# PowerConvert.net
KiCad netlist of a schematic drawn in Altium Designer
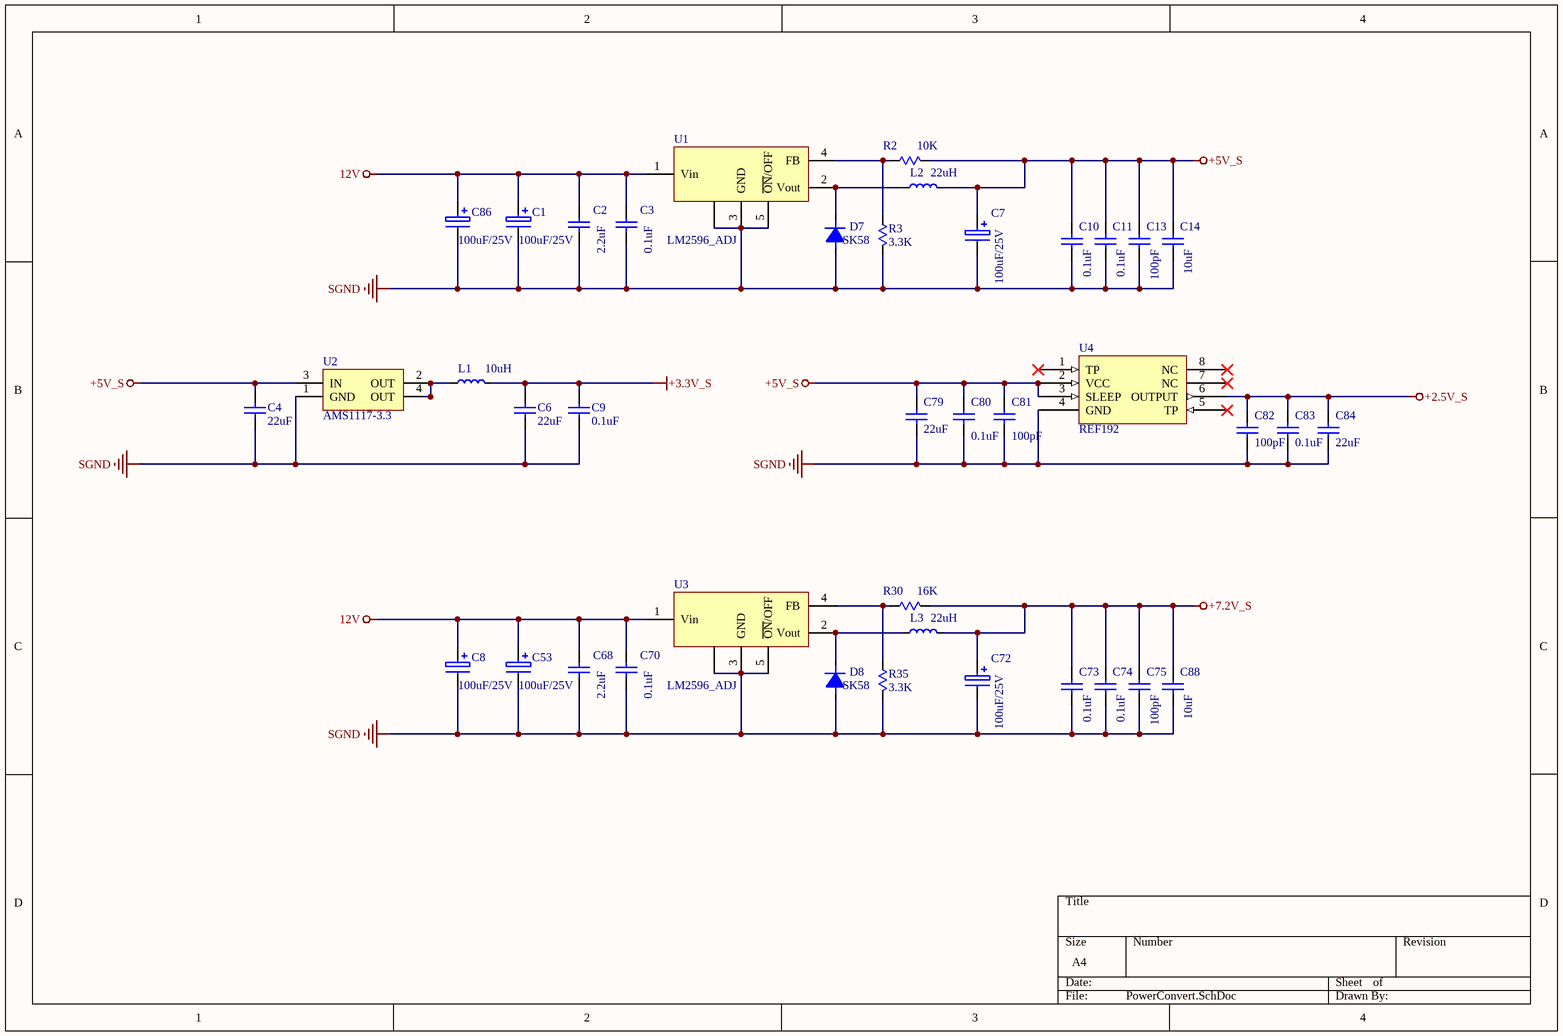
[diagram p0: PowerConvert.SchDoc]

(export (version "E")
  (design (tool "Eeschema 10.0.6"))
  (components
    (comp (ref "C1")
      (value "100uF/25V")
      (footprint "CT7343-E-S")
      (description "Electrolytic Capacitor")
      (libsource (lib "*") (part "ELECTRO"))
    )
    (comp (ref "C2")
      (value "2.2uF")
      (footprint "C1206")
      (description "CAP")
      (fields (field (name "PUBLISHER") "Altium Limited"))
      (libsource (lib "Passive Components Class") (part "CAP"))
    )
    (comp (ref "C3")
      (value "0.1uF")
      (footprint "C0805")
      (description "CAP")
      (fields (field (name "PUBLISHER") "Altium Limited"))
      (libsource (lib "Passive Components Class") (part "CAP"))
    )
    (comp (ref "C4")
      (value "22uF")
      (footprint "C1206")
      (description "CAP")
      (fields (field (name "PUBLISHER") "Altium Limited"))
      (libsource (lib "Passive Components Class") (part "CAP"))
    )
    (comp (ref "C6")
      (value "22uF")
      (footprint "C1206")
      (description "CAP")
      (fields (field (name "PUBLISHER") "Altium Limited"))
      (libsource (lib "Passive Components Class") (part "CAP"))
    )
    (comp (ref "C7")
      (value "100uF/25V")
      (footprint "CT7343-E-S")
      (description "Electrolytic Capacitor")
      (libsource (lib "*") (part "ELECTRO"))
    )
    (comp (ref "C8")
      (value "100uF/25V")
      (footprint "CT7343-E-S")
      (description "Electrolytic Capacitor")
      (libsource (lib "*") (part "ELECTRO"))
    )
    (comp (ref "C9")
      (value "0.1uF")
      (footprint "C0805")
      (description "CAP")
      (fields (field (name "PUBLISHER") "Altium Limited"))
      (libsource (lib "Passive Components Class") (part "CAP"))
    )
    (comp (ref "C10")
      (value "0.1uF")
      (footprint "C0805")
      (description "CAP")
      (fields (field (name "PUBLISHER") "Altium Limited"))
      (libsource (lib "Passive Components Class") (part "CAP"))
    )
    (comp (ref "C11")
      (value "0.1uF")
      (footprint "C0805")
      (description "CAP")
      (fields (field (name "PUBLISHER") "Altium Limited"))
      (libsource (lib "Passive Components Class") (part "CAP"))
    )
    (comp (ref "C13")
      (value "100pF")
      (footprint "C0805")
      (description "CAP")
      (fields (field (name "PUBLISHER") "Altium Limited"))
      (libsource (lib "Passive Components Class") (part "CAP"))
    )
    (comp (ref "C14")
      (value "10uF")
      (footprint "C0805")
      (description "CAP")
      (fields (field (name "PUBLISHER") "Altium Limited"))
      (libsource (lib "Passive Components Class") (part "CAP"))
    )
    (comp (ref "C53")
      (value "100uF/25V")
      (footprint "CT7343-E-S")
      (description "Electrolytic Capacitor")
      (libsource (lib "*") (part "ELECTRO"))
    )
    (comp (ref "C68")
      (value "2.2uF")
      (footprint "C1206")
      (description "CAP")
      (fields (field (name "PUBLISHER") "Altium Limited"))
      (libsource (lib "Passive Components Class") (part "CAP"))
    )
    (comp (ref "C70")
      (value "0.1uF")
      (footprint "C0805")
      (description "CAP")
      (fields (field (name "PUBLISHER") "Altium Limited"))
      (libsource (lib "Passive Components Class") (part "CAP"))
    )
    (comp (ref "C72")
      (value "100uF/25V")
      (footprint "CT7343-E-S")
      (description "Electrolytic Capacitor")
      (libsource (lib "*") (part "ELECTRO"))
    )
    (comp (ref "C73")
      (value "0.1uF")
      (footprint "C0805")
      (description "CAP")
      (fields (field (name "PUBLISHER") "Altium Limited"))
      (libsource (lib "Passive Components Class") (part "CAP"))
    )
    (comp (ref "C74")
      (value "0.1uF")
      (footprint "C0805")
      (description "CAP")
      (fields (field (name "PUBLISHER") "Altium Limited"))
      (libsource (lib "Passive Components Class") (part "CAP"))
    )
    (comp (ref "C75")
      (value "100pF")
      (footprint "C0805")
      (description "CAP")
      (fields (field (name "PUBLISHER") "Altium Limited"))
      (libsource (lib "Passive Components Class") (part "CAP"))
    )
    (comp (ref "C79")
      (value "22uF")
      (footprint "C1206")
      (description "CAP")
      (fields (field (name "PUBLISHER") "Altium Limited"))
      (libsource (lib "Passive Components Class") (part "CAP"))
    )
    (comp (ref "C80")
      (value "0.1uF")
      (footprint "C0805")
      (description "CAP")
      (fields (field (name "PUBLISHER") "Altium Limited"))
      (libsource (lib "Passive Components Class") (part "CAP"))
    )
    (comp (ref "C81")
      (value "100pF")
      (footprint "C0805")
      (description "CAP")
      (fields (field (name "PUBLISHER") "Altium Limited"))
      (libsource (lib "Passive Components Class") (part "CAP"))
    )
    (comp (ref "C82")
      (value "100pF")
      (footprint "C0805")
      (description "CAP")
      (fields (field (name "PUBLISHER") "Altium Limited"))
      (libsource (lib "Passive Components Class") (part "CAP"))
    )
    (comp (ref "C83")
      (value "0.1uF")
      (footprint "C0805")
      (description "CAP")
      (fields (field (name "PUBLISHER") "Altium Limited"))
      (libsource (lib "Passive Components Class") (part "CAP"))
    )
    (comp (ref "C84")
      (value "22uF")
      (footprint "C1206")
      (description "CAP")
      (fields (field (name "PUBLISHER") "Altium Limited"))
      (libsource (lib "Passive Components Class") (part "CAP"))
    )
    (comp (ref "C86")
      (value "100uF/25V")
      (footprint "CT7343-E-S")
      (description "Electrolytic Capacitor")
      (libsource (lib "*") (part "ELECTRO"))
    )
    (comp (ref "C88")
      (value "10uF")
      (footprint "C0805")
      (description "CAP")
      (fields (field (name "PUBLISHER") "Altium Limited"))
      (libsource (lib "Passive Components Class") (part "CAP"))
    )
    (comp (ref "D7")
      (value "SK58")
      (footprint "SMB")
      (description "Diode")
      (libsource (lib "*") (part "DIODE1"))
    )
    (comp (ref "D8")
      (value "SK58")
      (footprint "SMB")
      (description "Diode")
      (libsource (lib "*") (part "DIODE1"))
    )
    (comp (ref "L1")
      (value "10uH")
      (footprint "L0805-C")
      (description "INDUCTOR")
      (fields (field (name "PUBLISHER") "Altium Limited"))
      (libsource (lib "Passive Components Class") (part "INDUCTOR"))
    )
    (comp (ref "L2")
      (value "22uH")
      (footprint "L5050-P")
      (description "INDUCTOR")
      (fields (field (name "PUBLISHER") "Altium Limited"))
      (libsource (lib "Passive Components Class") (part "INDUCTOR"))
    )
    (comp (ref "L3")
      (value "22uH")
      (footprint "L5050-P")
      (description "INDUCTOR")
      (fields (field (name "PUBLISHER") "Altium Limited"))
      (libsource (lib "Passive Components Class") (part "INDUCTOR"))
    )
    (comp (ref "R2")
      (value "10K")
      (footprint "R0805")
      (description "Resistor")
      (fields (field (name "PUBLISHER") "Altium Limited"))
      (libsource (lib "Passive Components Class") (part "RES"))
    )
    (comp (ref "R3")
      (value "3.3K")
      (footprint "R0805")
      (description "Resistor")
      (fields (field (name "PUBLISHER") "Altium Limited"))
      (libsource (lib "Passive Components Class") (part "RES"))
    )
    (comp (ref "R30")
      (value "16K")
      (footprint "R0805")
      (description "Resistor")
      (fields (field (name "PUBLISHER") "Altium Limited"))
      (libsource (lib "Passive Components Class") (part "RES"))
    )
    (comp (ref "R35")
      (value "3.3K")
      (footprint "R0805")
      (description "Resistor")
      (fields (field (name "PUBLISHER") "Altium Limited"))
      (libsource (lib "Passive Components Class") (part "RES"))
    )
    (comp (ref "U1") (value "LM2596_ADJ") (footprint "TO263") (libsource (lib "*") (part "LM2575")))
    (comp (ref "U2")
      (value "AMS1117-3.3")
      (footprint "SOT-223")
      (description "800mA and 1A Low Dropout Positive Regulator 2.85V, 3.3V, 5V, and Adjustable")
      (fields (field (name "PUBLISHER") "Altium Limited"))
      (libsource (lib "BB Power Mgt Voltage Regulator") (part "REG1117-3.3"))
    )
    (comp (ref "U3") (value "LM2596_ADJ") (footprint "TO263") (libsource (lib "*") (part "LM2575")))
    (comp (ref "U4") (value "REF192") (footprint "SO-8") (libsource (lib "tribute") (part "REF192/5/7")))
  )
  (nets
    (net (code "1") (name "+2.5V_S") (class "Default")
      (node (ref "C82") (pin "2") (pinfunction "2_2") (pintype "passive"))
      (node (ref "C83") (pin "2") (pinfunction "2_2") (pintype "passive"))
      (node (ref "C84") (pin "2") (pinfunction "2_2") (pintype "passive"))
      (node (ref "U4") (pin "6") (pinfunction "OUTPUT_6") (pintype "output"))
    )
    (net (code "2") (name "+3.3V_S") (class "Default")
      (node (ref "C6") (pin "1") (pinfunction "1_1") (pintype "passive"))
      (node (ref "C9") (pin "2") (pinfunction "2_2") (pintype "passive"))
      (node (ref "L1") (pin "1") (pinfunction "1_1") (pintype "passive"))
    )
    (net (code "3") (name "+5V_S") (class "Default")
      (node (ref "C10") (pin "2") (pinfunction "2_2") (pintype "passive"))
      (node (ref "C11") (pin "2") (pinfunction "2_2") (pintype "passive"))
      (node (ref "C13") (pin "2") (pinfunction "2_2") (pintype "passive"))
      (node (ref "C14") (pin "2") (pinfunction "2_2") (pintype "passive"))
      (node (ref "C4") (pin "1") (pinfunction "1_1") (pintype "passive"))
      (node (ref "C7") (pin "1") (pinfunction "1_1") (pintype "passive"))
      (node (ref "C79") (pin "2") (pinfunction "2_2") (pintype "passive"))
      (node (ref "C80") (pin "2") (pinfunction "2_2") (pintype "passive"))
      (node (ref "C81") (pin "2") (pinfunction "2_2") (pintype "passive"))
      (node (ref "L2") (pin "1") (pinfunction "1_1") (pintype "passive"))
      (node (ref "R2") (pin "1") (pinfunction "1_1") (pintype "passive"))
      (node (ref "U2") (pin "3") (pinfunction "IN_3") (pintype "power_in"))
      (node (ref "U4") (pin "2") (pinfunction "VCC_2") (pintype "input"))
      (node (ref "U4") (pin "3") (pinfunction "SLEEP_3") (pintype "input"))
    )
    (net (code "4") (name "+7.2V_S") (class "Default")
      (node (ref "C72") (pin "1") (pinfunction "1_1") (pintype "passive"))
      (node (ref "C73") (pin "2") (pinfunction "2_2") (pintype "passive"))
      (node (ref "C74") (pin "2") (pinfunction "2_2") (pintype "passive"))
      (node (ref "C75") (pin "2") (pinfunction "2_2") (pintype "passive"))
      (node (ref "C88") (pin "2") (pinfunction "2_2") (pintype "passive"))
      (node (ref "L3") (pin "1") (pinfunction "1_1") (pintype "passive"))
      (node (ref "R30") (pin "1") (pinfunction "1_1") (pintype "passive"))
    )
    (net (code "5") (name "12V") (class "Default")
      (node (ref "C1") (pin "1") (pinfunction "1_1") (pintype "passive"))
      (node (ref "C2") (pin "2") (pinfunction "2_2") (pintype "passive"))
      (node (ref "C3") (pin "2") (pinfunction "2_2") (pintype "passive"))
      (node (ref "C53") (pin "1") (pinfunction "1_1") (pintype "passive"))
      (node (ref "C68") (pin "2") (pinfunction "2_2") (pintype "passive"))
      (node (ref "C70") (pin "2") (pinfunction "2_2") (pintype "passive"))
      (node (ref "C8") (pin "1") (pinfunction "1_1") (pintype "passive"))
      (node (ref "C86") (pin "1") (pinfunction "1_1") (pintype "passive"))
      (node (ref "U1") (pin "1") (pinfunction "Vin_1") (pintype "power_in"))
      (node (ref "U3") (pin "1") (pinfunction "Vin_1") (pintype "power_in"))
    )
    (net (code "6") (name "Net-(D7-K)") (class "Default")
      (node (ref "D7") (pin "2") (pinfunction "K_2") (pintype "passive"))
      (node (ref "L2") (pin "2") (pinfunction "2_2") (pintype "passive"))
      (node (ref "U1") (pin "2") (pinfunction "Vout_2") (pintype "power_in"))
    )
    (net (code "7") (name "Net-(D8-K)") (class "Default")
      (node (ref "D8") (pin "2") (pinfunction "K_2") (pintype "passive"))
      (node (ref "L3") (pin "2") (pinfunction "2_2") (pintype "passive"))
      (node (ref "U3") (pin "2") (pinfunction "Vout_2") (pintype "power_in"))
    )
    (net (code "8") (name "Net-(L1-Pad2)") (class "Default")
      (node (ref "L1") (pin "2") (pinfunction "2_2") (pintype "passive"))
      (node (ref "U2") (pin "2") (pinfunction "OUT_2") (pintype "power_in"))
      (node (ref "U2") (pin "4") (pinfunction "OUT_4") (pintype "power_in"))
    )
    (net (code "9") (name "Net-(U1-FB)") (class "Default")
      (node (ref "R2") (pin "2") (pinfunction "2_2") (pintype "passive"))
      (node (ref "R3") (pin "2") (pinfunction "2_2") (pintype "passive"))
      (node (ref "U1") (pin "4") (pinfunction "FB_4") (pintype "passive"))
    )
    (net (code "10") (name "Net-(U3-FB)") (class "Default")
      (node (ref "R30") (pin "2") (pinfunction "2_2") (pintype "passive"))
      (node (ref "R35") (pin "2") (pinfunction "2_2") (pintype "passive"))
      (node (ref "U3") (pin "4") (pinfunction "FB_4") (pintype "passive"))
    )
    (net (code "11") (name "SGND") (class "Default")
      (node (ref "C1") (pin "2") (pinfunction "2_2") (pintype "passive"))
      (node (ref "C10") (pin "1") (pinfunction "1_1") (pintype "passive"))
      (node (ref "C11") (pin "1") (pinfunction "1_1") (pintype "passive"))
      (node (ref "C13") (pin "1") (pinfunction "1_1") (pintype "passive"))
      (node (ref "C14") (pin "1") (pinfunction "1_1") (pintype "passive"))
      (node (ref "C2") (pin "1") (pinfunction "1_1") (pintype "passive"))
      (node (ref "C3") (pin "1") (pinfunction "1_1") (pintype "passive"))
      (node (ref "C4") (pin "2") (pinfunction "2_2") (pintype "passive"))
      (node (ref "C53") (pin "2") (pinfunction "2_2") (pintype "passive"))
      (node (ref "C6") (pin "2") (pinfunction "2_2") (pintype "passive"))
      (node (ref "C68") (pin "1") (pinfunction "1_1") (pintype "passive"))
      (node (ref "C7") (pin "2") (pinfunction "2_2") (pintype "passive"))
      (node (ref "C70") (pin "1") (pinfunction "1_1") (pintype "passive"))
      (node (ref "C72") (pin "2") (pinfunction "2_2") (pintype "passive"))
      (node (ref "C73") (pin "1") (pinfunction "1_1") (pintype "passive"))
      (node (ref "C74") (pin "1") (pinfunction "1_1") (pintype "passive"))
      (node (ref "C75") (pin "1") (pinfunction "1_1") (pintype "passive"))
      (node (ref "C79") (pin "1") (pinfunction "1_1") (pintype "passive"))
      (node (ref "C8") (pin "2") (pinfunction "2_2") (pintype "passive"))
      (node (ref "C80") (pin "1") (pinfunction "1_1") (pintype "passive"))
      (node (ref "C81") (pin "1") (pinfunction "1_1") (pintype "passive"))
      (node (ref "C82") (pin "1") (pinfunction "1_1") (pintype "passive"))
      (node (ref "C83") (pin "1") (pinfunction "1_1") (pintype "passive"))
      (node (ref "C84") (pin "1") (pinfunction "1_1") (pintype "passive"))
      (node (ref "C86") (pin "2") (pinfunction "2_2") (pintype "passive"))
      (node (ref "C88") (pin "1") (pinfunction "1_1") (pintype "passive"))
      (node (ref "C9") (pin "1") (pinfunction "1_1") (pintype "passive"))
      (node (ref "D7") (pin "1") (pinfunction "A_1") (pintype "passive"))
      (node (ref "D8") (pin "1") (pinfunction "A_1") (pintype "passive"))
      (node (ref "R3") (pin "1") (pinfunction "1_1") (pintype "passive"))
      (node (ref "R35") (pin "1") (pinfunction "1_1") (pintype "passive"))
      (node (ref "U1") (pin "0") (pinfunction "GND_0") (pintype "passive"))
      (node (ref "U1") (pin "3") (pinfunction "GND_3") (pintype "power_in"))
      (node (ref "U1") (pin "5") (pinfunction "~{ON}/OFF_5") (pintype "passive"))
      (node (ref "U2") (pin "1") (pinfunction "GND_1") (pintype "power_in"))
      (node (ref "U3") (pin "0") (pinfunction "GND_0") (pintype "passive"))
      (node (ref "U3") (pin "3") (pinfunction "GND_3") (pintype "power_in"))
      (node (ref "U3") (pin "5") (pinfunction "~{ON}/OFF_5") (pintype "passive"))
      (node (ref "U4") (pin "4") (pinfunction "GND_4") (pintype "power_in"))
    )
    (net (code "12") (name "unconnected-(U4-NC-Pad7)") (class "Default")
      (node (ref "U4") (pin "7") (pinfunction "NC_7") (pintype "passive+no_connect"))
    )
    (net (code "13") (name "unconnected-(U4-NC-Pad8)") (class "Default")
      (node (ref "U4") (pin "8") (pinfunction "NC_8") (pintype "passive+no_connect"))
    )
    (net (code "14") (name "unconnected-(U4-TP-Pad1)") (class "Default")
      (node (ref "U4") (pin "1") (pinfunction "TP_1") (pintype "input+no_connect"))
    )
    (net (code "15") (name "unconnected-(U4-TP-Pad5)") (class "Default")
      (node (ref "U4") (pin "5") (pinfunction "TP_5") (pintype "input+no_connect"))
    )
  )
)
